# Breadboard.net
KiCad netlist of a schematic drawn in EAGLE
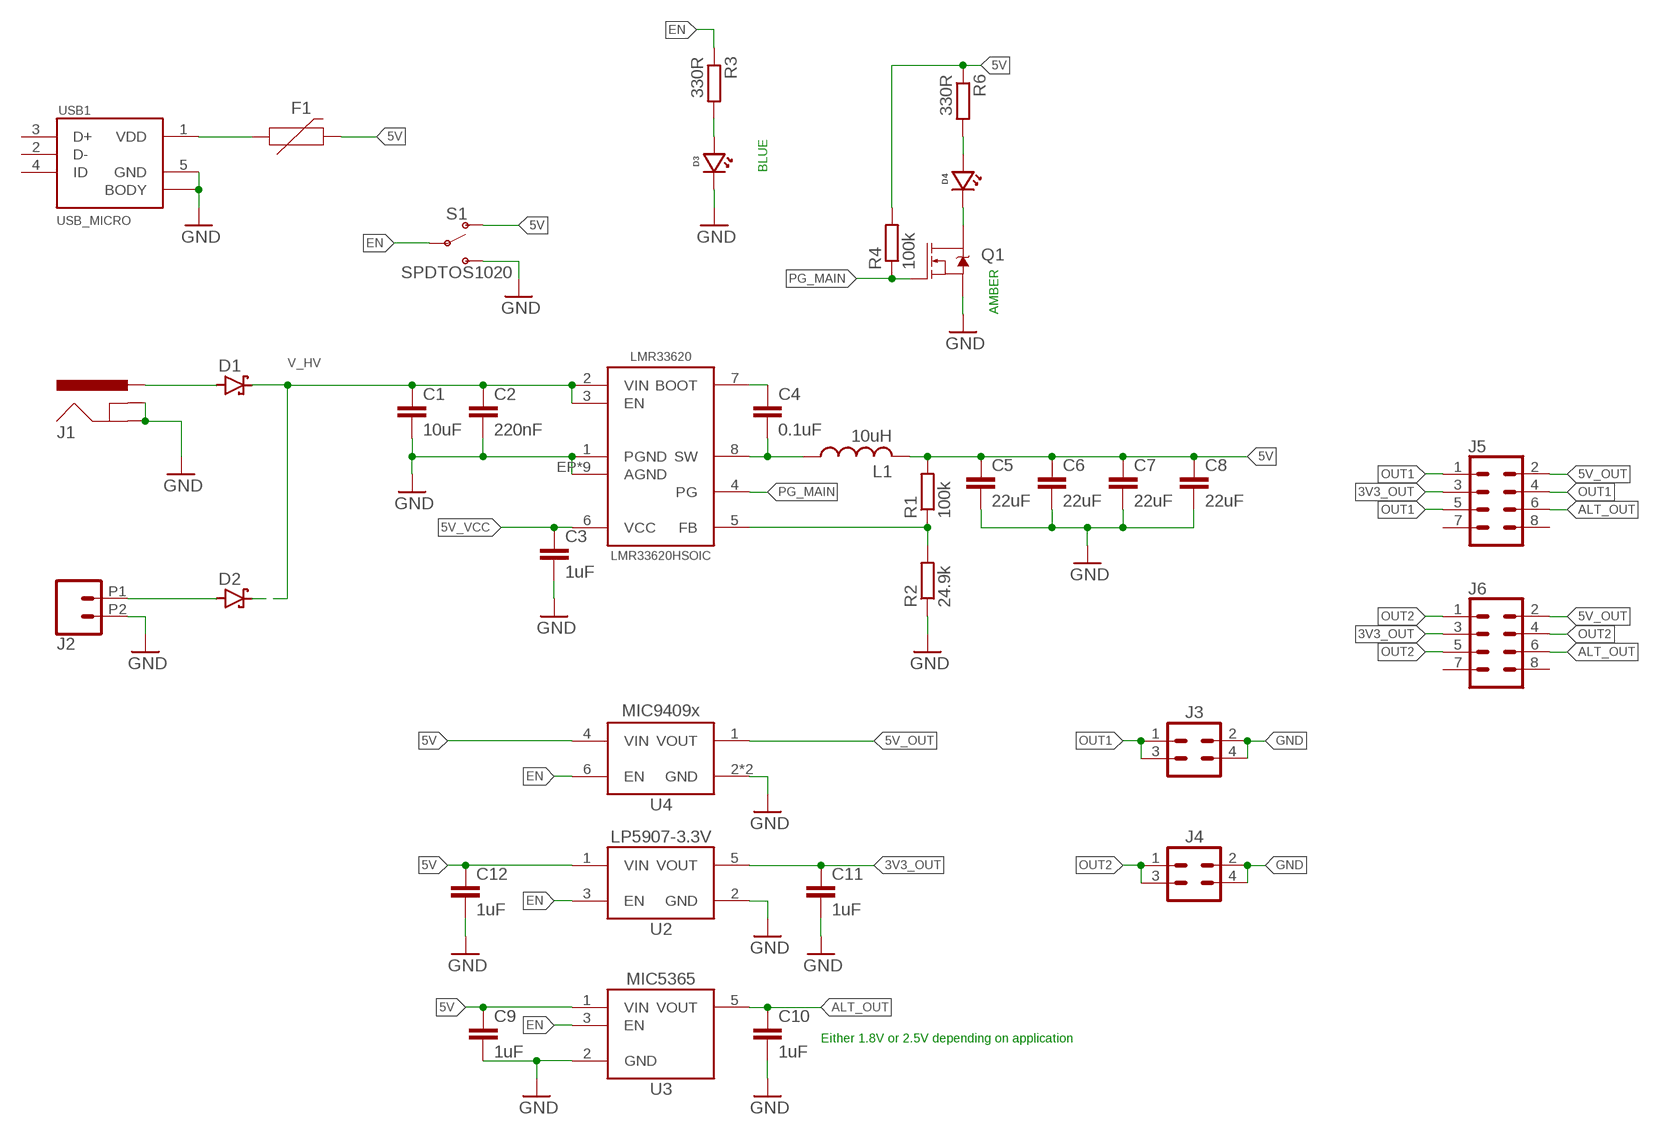
[diagram p0: schematic, sheet 1]

(export (version "E")
  (design (tool "Eeschema 10.0.6"))
  (components
    (comp (ref "C1")
      (value "10uF")
      (footprint "eagle-import:C0805")
      (fields (field (name "MF") "Murata") (field (name "MPN") "GRM21BR61C106KE15K"))
      (libsource (lib "eagle-import") (part "C-EUC080510UF"))
    )
    (comp (ref "C2")
      (value "220nF")
      (footprint "eagle-import:C0603")
      (libsource (lib "eagle-import") (part "C-EUC0603"))
    )
    (comp (ref "C3")
      (value "1uF")
      (footprint "eagle-import:C0603")
      (fields (field (name "MF") "Yaiyo Yuden") (field (name "MPN") "EMK107BJ105KA-T"))
      (libsource (lib "eagle-import") (part "C-EUC06031UF"))
    )
    (comp (ref "C4")
      (value "0.1uF")
      (footprint "eagle-import:C0603")
      (fields (field (name "MF") "Murata") (field (name "MPN") "GCM188R71E104KA57D"))
      (libsource (lib "eagle-import") (part "C-EUC06030.1UF"))
    )
    (comp (ref "C5")
      (value "22uF")
      (footprint "eagle-import:C0805")
      (fields (field (name "MF") "Murata") (field (name "MPN") "GRM219R61C226ME15L"))
      (libsource (lib "eagle-import") (part "C-EUC080522UF"))
    )
    (comp (ref "C6")
      (value "22uF")
      (footprint "eagle-import:C0805")
      (fields (field (name "MF") "Murata") (field (name "MPN") "GRM219R61C226ME15L"))
      (libsource (lib "eagle-import") (part "C-EUC080522UF"))
    )
    (comp (ref "C7")
      (value "22uF")
      (footprint "eagle-import:C0805")
      (fields (field (name "MF") "Murata") (field (name "MPN") "GRM219R61C226ME15L"))
      (libsource (lib "eagle-import") (part "C-EUC080522UF"))
    )
    (comp (ref "C8")
      (value "22uF")
      (footprint "eagle-import:C0805")
      (fields (field (name "MF") "Murata") (field (name "MPN") "GRM219R61C226ME15L"))
      (libsource (lib "eagle-import") (part "C-EUC080522UF"))
    )
    (comp (ref "C9")
      (value "1uF")
      (footprint "eagle-import:C0603")
      (fields (field (name "MF") "Yaiyo Yuden") (field (name "MPN") "EMK107BJ105KA-T"))
      (libsource (lib "eagle-import") (part "C-EUC06031UF"))
    )
    (comp (ref "C10")
      (value "1uF")
      (footprint "eagle-import:C0603")
      (fields (field (name "MF") "Yaiyo Yuden") (field (name "MPN") "EMK107BJ105KA-T"))
      (libsource (lib "eagle-import") (part "C-EUC06031UF"))
    )
    (comp (ref "C11")
      (value "1uF")
      (footprint "eagle-import:C0603")
      (fields (field (name "MF") "Yaiyo Yuden") (field (name "MPN") "EMK107BJ105KA-T"))
      (libsource (lib "eagle-import") (part "C-EUC06031UF"))
    )
    (comp (ref "C12")
      (value "1uF")
      (footprint "eagle-import:C0603")
      (fields (field (name "MF") "Yaiyo Yuden") (field (name "MPN") "EMK107BJ105KA-T"))
      (libsource (lib "eagle-import") (part "C-EUC06031UF"))
    )
    (comp (ref "D1")
      (value "DIODE_SCHOTTKYSOD-123")
      (footprint "eagle-import:SOD-123")
      (libsource (lib "eagle-import") (part "DIODE_SCHOTTKYSOD-123"))
    )
    (comp (ref "D2")
      (value "DIODE_SCHOTTKYSOD-123")
      (footprint "eagle-import:SOD-123")
      (libsource (lib "eagle-import") (part "DIODE_SCHOTTKYSOD-123"))
    )
    (comp (ref "D3")
      (value "LEDBLUE0603")
      (footprint "eagle-import:LED_0603")
      (fields (field (name "MF") "Wurth") (field (name "MPN") "150060BS75000"))
      (libsource (lib "eagle-import") (part "LED0603BLUE"))
    )
    (comp (ref "D4")
      (value "LEDAMBER0603")
      (footprint "eagle-import:LED_0603")
      (fields (field (name "MF") "Wurth") (field (name "MPN") "150060AS75000"))
      (libsource (lib "eagle-import") (part "LED0603AMBER"))
    )
    (comp (ref "F1")
      (value "PPTC_HALF-AMP")
      (footprint "eagle-import:1206")
      (fields (field (name "MF") "Bourns") (field (name "MPN") "MF-NSMF020-2"))
      (libsource (lib "eagle-import") (part "PPTC_HALF-AMP"))
    )
    (comp (ref "J1")
      (value "POWER_JACKSLT")
      (footprint "eagle-import:POWER_JACK_SLOT")
      (libsource (lib "eagle-import") (part "POWER_JACKSLT"))
    )
    (comp (ref "J2")
      (value "CONN_022.54_SCREW")
      (footprint "eagle-import:1X02_2.54_SCREWTERM")
      (fields (field (name "MF") "OnShore") (field (name "MPN") "OSTVN02A150"))
      (libsource (lib "eagle-import") (part "CONN_022.54_SCREW"))
    )
    (comp (ref "J3")
      (value "CONN_2X2")
      (footprint "eagle-import:2X02")
      (libsource (lib "eagle-import") (part "CONN_2X2"))
    )
    (comp (ref "J4")
      (value "CONN_2X2")
      (footprint "eagle-import:2X02")
      (libsource (lib "eagle-import") (part "CONN_2X2"))
    )
    (comp (ref "J5")
      (value "CONN_04X2")
      (footprint "eagle-import:2X4")
      (libsource (lib "eagle-import") (part "CONN_04X2"))
    )
    (comp (ref "J6")
      (value "CONN_04X2")
      (footprint "eagle-import:2X4")
      (libsource (lib "eagle-import") (part "CONN_04X2"))
    )
    (comp (ref "L1")
      (value "10uH")
      (footprint "eagle-import:WE-LQS(5X5)")
      (libsource (lib "eagle-import") (part "INDUCTORLQS_5X5"))
    )
    (comp (ref "Q1")
      (value "MOSFET-NCH-2N7002P")
      (footprint "eagle-import:SOT23-3")
      (fields (field (name "MF") "Nexperia") (field (name "MPN") "2N7002P,215"))
      (libsource (lib "eagle-import") (part "MOSFET-NCH-2N7002P"))
    )
    (comp (ref "R1")
      (value "100k")
      (footprint "eagle-import:R0603")
      (fields (field (name "MF") "Yageo") (field (name "MPN") "RC0603FR-07100KL"))
      (libsource (lib "eagle-import") (part "R-EU_R0603100K"))
    )
    (comp (ref "R2")
      (value "24.9k")
      (footprint "eagle-import:R0603")
      (fields (field (name "MF") "Yageo"))
      (libsource (lib "eagle-import") (part "R-EU_R0603"))
    )
    (comp (ref "R3")
      (value "330R")
      (footprint "eagle-import:R0603")
      (fields
        (field (name "MF") "Yageo")
        (field (name "MPN") "RC0603FR-07330RL")
        (field (name "VALUE_PART") "330")
      )
      (libsource (lib "eagle-import") (part "R-EU_R0603330"))
    )
    (comp (ref "R4")
      (value "100k")
      (footprint "eagle-import:R0603")
      (fields (field (name "MF") "Yageo") (field (name "MPN") "RC0603FR-07100KL"))
      (libsource (lib "eagle-import") (part "R-EU_R0603100K"))
    )
    (comp (ref "R6")
      (value "330R")
      (footprint "eagle-import:R0603")
      (fields
        (field (name "MF") "Yageo")
        (field (name "MPN") "RC0603FR-07330RL")
        (field (name "VALUE_PART") "330")
      )
      (libsource (lib "eagle-import") (part "R-EU_R0603330"))
    )
    (comp (ref "S1")
      (value "SPDTOS1020")
      (footprint "eagle-import:OS102011MS2QN1")
      (libsource (lib "eagle-import") (part "SPDTOS1020"))
    )
    (comp (ref "U1")
      (value "LMR33620HSOIC")
      (footprint "eagle-import:DDS0008J")
      (fields (field (name "MF") "TI") (field (name "MPN") "LMR33620CDDAR"))
      (libsource (lib "eagle-import") (part "LMR33620HSOIC"))
    )
    (comp (ref "U2")
      (value "LP59073.3VDBV")
      (footprint "eagle-import:SOT23-5")
      (fields
        (field (name "DISP") "LP5907-3.3V")
        (field (name "MF") "TI")
        (field (name "MPN") "LP5907MFX-3.3/NOPB")
      )
      (libsource (lib "eagle-import") (part "LP5907DBV3.3V"))
    )
    (comp (ref "U3")
      (value "MIC53651.8SOT23")
      (footprint "eagle-import:SOT23-5")
      (fields (field (name "MF") "Microchip") (field (name "MPN") "MIC5365-1.8YD5-TR"))
      (libsource (lib "eagle-import") (part "MIC5365SOT231.8"))
    )
    (comp (ref "U4")
      (value "MIC9409C6")
      (footprint "eagle-import:SC-70_6")
      (fields (field (name "DISP") "MIC9409x") (field (name "MF") "Microchip"))
      (libsource (lib "eagle-import") (part "MIC9409C6"))
    )
    (comp (ref "USB1")
      (value "USB_MICRO")
      (footprint "eagle-import:10118194-0001LF_10118194-0001LF_LONGER_PADS")
      (fields (field (name "MF") "Amphenol") (field (name "MPN") "10118194-0001LF"))
      (libsource (lib "eagle-import") (part "USB_MICRO"))
    )
  )
  (nets
    (net (code "1") (name "/V_HV") (class "Default")
      (node (ref "C1") (pin "1") (pinfunction "1_1") (pintype "passive"))
      (node (ref "C2") (pin "1") (pinfunction "1_1") (pintype "passive"))
      (node (ref "D1") (pin "CAT") (pinfunction "C_CAT") (pintype "passive"))
      (node (ref "D2") (pin "CAT") (pinfunction "C_CAT") (pintype "passive"))
      (node (ref "U1") (pin "2") (pinfunction "VIN_2") (pintype "power_in"))
      (node (ref "U1") (pin "3") (pinfunction "EN_3") (pintype "input"))
    )
    (net (code "2") (name "3V3_OUT") (class "Default")
      (node (ref "C11") (pin "1") (pinfunction "1_1") (pintype "passive"))
      (node (ref "J5") (pin "3") (pinfunction "3_3") (pintype "passive"))
      (node (ref "J6") (pin "3") (pinfunction "3_3") (pintype "passive"))
      (node (ref "U2") (pin "5") (pinfunction "VOUT_5") (pintype "power_in"))
    )
    (net (code "3") (name "5V") (class "Default")
      (node (ref "C12") (pin "1") (pinfunction "1_1") (pintype "passive"))
      (node (ref "C5") (pin "1") (pinfunction "1_1") (pintype "passive"))
      (node (ref "C6") (pin "1") (pinfunction "1_1") (pintype "passive"))
      (node (ref "C7") (pin "1") (pinfunction "1_1") (pintype "passive"))
      (node (ref "C8") (pin "1") (pinfunction "1_1") (pintype "passive"))
      (node (ref "C9") (pin "1") (pinfunction "1_1") (pintype "passive"))
      (node (ref "F1") (pin "2") (pinfunction "2_2") (pintype "bidirectional"))
      (node (ref "L1") (pin "2") (pinfunction "2_2") (pintype "passive"))
      (node (ref "R1") (pin "2") (pinfunction "2_2") (pintype "passive"))
      (node (ref "R4") (pin "2") (pinfunction "2_2") (pintype "passive"))
      (node (ref "R6") (pin "1") (pinfunction "1_1") (pintype "passive"))
      (node (ref "S1") (pin "1") (pinfunction "O_1") (pintype "passive"))
      (node (ref "U2") (pin "1") (pinfunction "VIN_1") (pintype "power_in"))
      (node (ref "U3") (pin "1") (pinfunction "VIN_1") (pintype "power_in"))
      (node (ref "U4") (pin "4") (pinfunction "VIN_4") (pintype "power_in"))
    )
    (net (code "4") (name "5V_OUT") (class "Default")
      (node (ref "J5") (pin "2") (pinfunction "2_2") (pintype "passive"))
      (node (ref "J6") (pin "2") (pinfunction "2_2") (pintype "passive"))
      (node (ref "U4") (pin "1") (pinfunction "VOUT_1") (pintype "power_in"))
    )
    (net (code "5") (name "5V_VCC") (class "Default")
      (node (ref "C3") (pin "1") (pinfunction "1_1") (pintype "passive"))
      (node (ref "U1") (pin "6") (pinfunction "VCC_6") (pintype "power_in"))
    )
    (net (code "6") (name "ALT_OUT") (class "Default")
      (node (ref "C10") (pin "1") (pinfunction "1_1") (pintype "passive"))
      (node (ref "J5") (pin "6") (pinfunction "6_6") (pintype "passive"))
      (node (ref "J6") (pin "6") (pinfunction "6_6") (pintype "passive"))
      (node (ref "U3") (pin "5") (pinfunction "VOUT_5") (pintype "power_in"))
    )
    (net (code "7") (name "EN") (class "Default")
      (node (ref "R3") (pin "1") (pinfunction "1_1") (pintype "passive"))
      (node (ref "S1") (pin "2") (pinfunction "P_2") (pintype "passive"))
      (node (ref "U2") (pin "3") (pinfunction "EN_3") (pintype "input"))
      (node (ref "U3") (pin "3") (pinfunction "EN_3") (pintype "input"))
      (node (ref "U4") (pin "6") (pinfunction "EN_6") (pintype "input"))
    )
    (net (code "8") (name "GND") (class "Default")
      (node (ref "C1") (pin "2") (pinfunction "2_2") (pintype "passive"))
      (node (ref "C10") (pin "2") (pinfunction "2_2") (pintype "passive"))
      (node (ref "C11") (pin "2") (pinfunction "2_2") (pintype "passive"))
      (node (ref "C12") (pin "2") (pinfunction "2_2") (pintype "passive"))
      (node (ref "C2") (pin "2") (pinfunction "2_2") (pintype "passive"))
      (node (ref "C3") (pin "2") (pinfunction "2_2") (pintype "passive"))
      (node (ref "C5") (pin "2") (pinfunction "2_2") (pintype "passive"))
      (node (ref "C6") (pin "2") (pinfunction "2_2") (pintype "passive"))
      (node (ref "C7") (pin "2") (pinfunction "2_2") (pintype "passive"))
      (node (ref "C8") (pin "2") (pinfunction "2_2") (pintype "passive"))
      (node (ref "C9") (pin "2") (pinfunction "2_2") (pintype "passive"))
      (node (ref "D3") (pin "CATHODE") (pinfunction "CATHODE_CATHODE") (pintype "power_in"))
      (node (ref "J1") (pin "GND@1") (pinfunction "GNDBREAK_GND@1") (pintype "bidirectional"))
      (node (ref "J1") (pin "GND@2") (pinfunction "GND_GND@2") (pintype "bidirectional"))
      (node (ref "J2") (pin "P2") (pinfunction "2_P2") (pintype "passive"))
      (node (ref "J3") (pin "2") (pinfunction "2_2") (pintype "bidirectional"))
      (node (ref "J3") (pin "4") (pinfunction "4_4") (pintype "bidirectional"))
      (node (ref "J4") (pin "2") (pinfunction "2_2") (pintype "bidirectional"))
      (node (ref "J4") (pin "4") (pinfunction "4_4") (pintype "bidirectional"))
      (node (ref "Q1") (pin "2") (pinfunction "S_2") (pintype "bidirectional"))
      (node (ref "R2") (pin "1") (pinfunction "1_1") (pintype "passive"))
      (node (ref "S1") (pin "3") (pinfunction "S_3") (pintype "passive"))
      (node (ref "U1") (pin "1") (pinfunction "PGND_1") (pintype "power_in"))
      (node (ref "U1") (pin "EP") (pinfunction "AGND_EP") (pintype "power_in"))
      (node (ref "U1") (pin "EP@1") (pinfunction "AGND_EP@1") (pintype "power_in"))
      (node (ref "U1") (pin "EP@2") (pinfunction "AGND_EP@2") (pintype "power_in"))
      (node (ref "U1") (pin "EP@3") (pinfunction "AGND_EP@3") (pintype "power_in"))
      (node (ref "U1") (pin "EP@4") (pinfunction "AGND_EP@4") (pintype "power_in"))
      (node (ref "U1") (pin "EP@5") (pinfunction "AGND_EP@5") (pintype "power_in"))
      (node (ref "U1") (pin "EP@6") (pinfunction "AGND_EP@6") (pintype "power_in"))
      (node (ref "U1") (pin "EP@7") (pinfunction "AGND_EP@7") (pintype "power_in"))
      (node (ref "U1") (pin "EP@8") (pinfunction "AGND_EP@8") (pintype "power_in"))
      (node (ref "U2") (pin "2") (pinfunction "GND_2") (pintype "power_in"))
      (node (ref "U3") (pin "2") (pinfunction "GND_2") (pintype "power_in"))
      (node (ref "U4") (pin "2") (pinfunction "GND_2") (pintype "power_in"))
      (node (ref "U4") (pin "5") (pinfunction "GND_5") (pintype "power_in"))
      (node (ref "USB1") (pin "5") (pinfunction "GND_5") (pintype "power_in"))
      (node (ref "USB1") (pin "BODY@1") (pinfunction "BODY_BODY@1") (pintype "bidirectional"))
      (node (ref "USB1") (pin "BODY@2") (pinfunction "BODY_BODY@2") (pintype "bidirectional"))
      (node (ref "USB1") (pin "BODY@3") (pinfunction "BODY_BODY@3") (pintype "bidirectional"))
      (node (ref "USB1") (pin "BODY@4") (pinfunction "BODY_BODY@4") (pintype "bidirectional"))
      (node (ref "USB1") (pin "BODY@7") (pinfunction "BODY_BODY@7") (pintype "bidirectional"))
      (node (ref "USB1") (pin "BODY@8") (pinfunction "BODY_BODY@8") (pintype "bidirectional"))
    )
    (net (code "9") (name "Net-(D1-A)") (class "Default")
      (node (ref "D1") (pin "ANODE") (pinfunction "A_ANODE") (pintype "passive"))
      (node (ref "J1") (pin "PWR") (pinfunction "PWR_PWR") (pintype "bidirectional"))
    )
    (net (code "10") (name "Net-(D2-A)") (class "Default")
      (node (ref "D2") (pin "ANODE") (pinfunction "A_ANODE") (pintype "passive"))
      (node (ref "J2") (pin "P1") (pinfunction "1_P1") (pintype "passive"))
    )
    (net (code "11") (name "Net-(D3-PadANODE)") (class "Default")
      (node (ref "D3") (pin "ANODE") (pinfunction "ANODE_ANODE") (pintype "power_in"))
      (node (ref "R3") (pin "2") (pinfunction "2_2") (pintype "passive"))
    )
    (net (code "12") (name "Net-(D4-PadANODE)") (class "Default")
      (node (ref "D4") (pin "ANODE") (pinfunction "ANODE_ANODE") (pintype "power_in"))
      (node (ref "R6") (pin "2") (pinfunction "2_2") (pintype "passive"))
    )
    (net (code "13") (name "Net-(Q1-D)") (class "Default")
      (node (ref "D4") (pin "CATHODE") (pinfunction "CATHODE_CATHODE") (pintype "power_in"))
      (node (ref "Q1") (pin "3") (pinfunction "D_3") (pintype "bidirectional"))
    )
    (net (code "14") (name "Net-(U1-BOOT)") (class "Default")
      (node (ref "C4") (pin "1") (pinfunction "1_1") (pintype "passive"))
      (node (ref "U1") (pin "7") (pinfunction "BOOT_7") (pintype "power_in"))
    )
    (net (code "15") (name "Net-(U1-FB)") (class "Default")
      (node (ref "R1") (pin "1") (pinfunction "1_1") (pintype "passive"))
      (node (ref "R2") (pin "2") (pinfunction "2_2") (pintype "passive"))
      (node (ref "U1") (pin "5") (pinfunction "FB_5") (pintype "input"))
    )
    (net (code "16") (name "Net-(U1-SW)") (class "Default")
      (node (ref "C4") (pin "2") (pinfunction "2_2") (pintype "passive"))
      (node (ref "L1") (pin "1") (pinfunction "1_1") (pintype "passive"))
      (node (ref "U1") (pin "8") (pinfunction "SW_8") (pintype "power_in"))
    )
    (net (code "17") (name "Net-(USB1-VDD)") (class "Default")
      (node (ref "F1") (pin "1") (pinfunction "1_1") (pintype "bidirectional"))
      (node (ref "USB1") (pin "1") (pinfunction "VDD_1") (pintype "power_in"))
    )
    (net (code "18") (name "OUT1") (class "Default")
      (node (ref "J3") (pin "1") (pinfunction "1_1") (pintype "bidirectional"))
      (node (ref "J3") (pin "3") (pinfunction "3_3") (pintype "bidirectional"))
      (node (ref "J5") (pin "1") (pinfunction "1_1") (pintype "passive"))
      (node (ref "J5") (pin "4") (pinfunction "4_4") (pintype "passive"))
      (node (ref "J5") (pin "5") (pinfunction "5_5") (pintype "passive"))
    )
    (net (code "19") (name "OUT2") (class "Default")
      (node (ref "J4") (pin "1") (pinfunction "1_1") (pintype "bidirectional"))
      (node (ref "J4") (pin "3") (pinfunction "3_3") (pintype "bidirectional"))
      (node (ref "J6") (pin "1") (pinfunction "1_1") (pintype "passive"))
      (node (ref "J6") (pin "4") (pinfunction "4_4") (pintype "passive"))
      (node (ref "J6") (pin "5") (pinfunction "5_5") (pintype "passive"))
    )
    (net (code "20") (name "PG_MAIN") (class "Default")
      (node (ref "Q1") (pin "1") (pinfunction "G_1") (pintype "bidirectional"))
      (node (ref "R4") (pin "1") (pinfunction "1_1") (pintype "passive"))
      (node (ref "U1") (pin "4") (pinfunction "PG_4") (pintype "open_collector"))
    )
    (net (code "21") (name "unconnected-(J5-Pad7)") (class "Default")
      (node (ref "J5") (pin "7") (pinfunction "7_7") (pintype "passive"))
    )
    (net (code "22") (name "unconnected-(J5-Pad8)") (class "Default")
      (node (ref "J5") (pin "8") (pinfunction "8_8") (pintype "passive"))
    )
    (net (code "23") (name "unconnected-(J6-Pad7)") (class "Default")
      (node (ref "J6") (pin "7") (pinfunction "7_7") (pintype "passive"))
    )
    (net (code "24") (name "unconnected-(J6-Pad8)") (class "Default")
      (node (ref "J6") (pin "8") (pinfunction "8_8") (pintype "passive"))
    )
    (net (code "25") (name "unconnected-(USB1-D+-Pad3)") (class "Default")
      (node (ref "USB1") (pin "3") (pinfunction "D+_3") (pintype "bidirectional"))
    )
    (net (code "26") (name "unconnected-(USB1-D--Pad2)") (class "Default")
      (node (ref "USB1") (pin "2") (pinfunction "D-_2") (pintype "bidirectional"))
    )
    (net (code "27") (name "unconnected-(USB1-ID-Pad4)") (class "Default")
      (node (ref "USB1") (pin "4") (pinfunction "ID_4") (pintype "passive"))
    )
  )
)
